# RS-485_Interface.net
KiCad netlist of a schematic drawn in Altium Designer
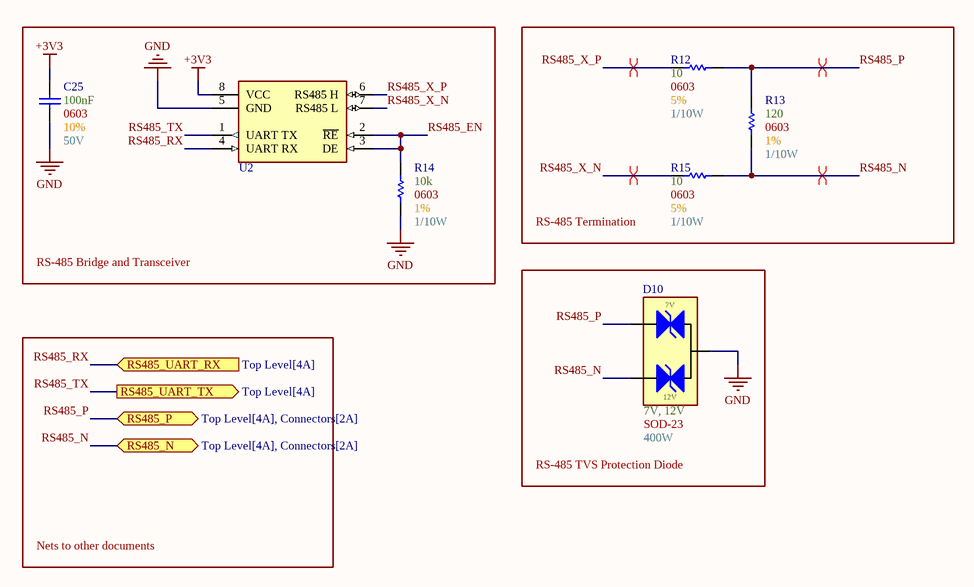
[diagram p0: RS-485 Interface.SchDoc]

(export (version "E")
  (design (tool "Eeschema 10.0.6"))
  (components
    (comp (ref "C25")
      (value "[Cap] 0603 0.1uF 10% 50V")
      (footprint "[Cap] SMD 0603")
      (description "CL10B104KB8NNNC")
      (fields
        (field (name "MAX VOLTAGE") "50V")
        (field (name "SIZE PACKAGE") "0603")
        (field (name "TOLERANCE") "10%")
        (field (name "CAPACITANCE") "100nF")
      )
      (libsource (lib "Capacitors") (part "[Cap] 0603 0.1uF 10% 50V"))
    )
    (comp (ref "D10")
      (value "SOD-23")
      (footprint "SOD-23")
      (description "CDSOT23-SM712")
      (fields (field (name "WATTAGE") "400W") (field (name "OPTIMAL ZENER VOLTAGE") "7V, 12V"))
      (libsource (lib "Diodes") (part "[TVS] 7,12Vnom 11,19Vclamp_max"))
    )
    (comp (ref "R12")
      (value "[10] SMD 0603 5% 1/10W")
      (footprint "[Res] SMD 0603")
      (description "RC0603JR-1310RL")
      (fields
        (field (name "WATTAGE") "1/10W")
        (field (name "TOLERANCE") "5%")
        (field (name "RESISTANCE") "10")
        (field (name "SIZE PACKAGE") "0603")
      )
      (libsource (lib "Resistors") (part "[10] SMD 0603 5% 1/10W"))
    )
    (comp (ref "R13")
      (value "[120] SMD 0603 1% 1/10W")
      (footprint "[Res] SMD 0603")
      (description "RC0603FR-07120RL")
      (fields
        (field (name "WATTAGE") "1/10W")
        (field (name "TOLERANCE") "1%")
        (field (name "RESISTANCE") "120")
        (field (name "SIZE PACKAGE") "0603")
      )
      (libsource (lib "Resistors") (part "[120] SMD 0603 1% 1/10W"))
    )
    (comp (ref "R14")
      (value "[10k] SMD 0603 1% 1/10W")
      (footprint "[Res] SMD 0603")
      (description "RMCF0603FT10K0")
      (fields
        (field (name "WATTAGE") "1/10W")
        (field (name "TOLERANCE") "1%")
        (field (name "RESISTANCE") "10k")
        (field (name "SIZE PACKAGE") "0603")
      )
      (libsource (lib "Resistors") (part "[10k] SMD 0603 1% 1/10W"))
    )
    (comp (ref "R15")
      (value "[10] SMD 0603 5% 1/10W")
      (footprint "[Res] SMD 0603")
      (description "RC0603JR-1310RL")
      (fields
        (field (name "WATTAGE") "1/10W")
        (field (name "TOLERANCE") "5%")
        (field (name "RESISTANCE") "10")
        (field (name "SIZE PACKAGE") "0603")
      )
      (libsource (lib "Resistors") (part "[10] SMD 0603 5% 1/10W"))
    )
    (comp (ref "U2")
      (value "[Bridge] UART-RS485")
      (footprint "8-SOIC")
      (description "THVD1400DR")
      (libsource (lib "ICs") (part "[Bridge] UART-RS485"))
    )
  )
  (nets
    (net (code "1") (name "+3V3") (class "Default")
      (node (ref "C25") (pin "2") (pinfunction "2_2") (pintype "passive"))
      (node (ref "U2") (pin "8") (pinfunction "VCC_8") (pintype "passive"))
    )
    (net (code "2") (name "/RS485_EN") (class "Default")
      (node (ref "R14") (pin "2") (pinfunction "2_2") (pintype "passive"))
      (node (ref "U2") (pin "2") (pinfunction "~{RE}_2") (pintype "input"))
      (node (ref "U2") (pin "3") (pinfunction "DE_3") (pintype "input"))
    )
    (net (code "3") (name "/RS485_N") (class "Default")
      (node (ref "D10") (pin "2") (pintype "passive"))
      (node (ref "R13") (pin "1") (pinfunction "1_1") (pintype "passive"))
      (node (ref "R15") (pin "1") (pinfunction "1_1") (pintype "passive"))
    )
    (net (code "4") (name "/RS485_P") (class "Default")
      (node (ref "D10") (pin "1") (pintype "passive"))
      (node (ref "R12") (pin "1") (pinfunction "1_1") (pintype "passive"))
      (node (ref "R13") (pin "2") (pinfunction "2_2") (pintype "passive"))
    )
    (net (code "5") (name "/RS485_RX") (class "Default")
      (node (ref "U2") (pin "4") (pinfunction "UART_RX_4") (pintype "input"))
    )
    (net (code "6") (name "/RS485_TX") (class "Default")
      (node (ref "U2") (pin "1") (pinfunction "UART_TX_1") (pintype "output"))
    )
    (net (code "7") (name "/RS485_X_N") (class "Default")
      (node (ref "R15") (pin "2") (pinfunction "2_2") (pintype "passive"))
      (node (ref "U2") (pin "7") (pinfunction "RS485_L_7") (pintype "bidirectional"))
    )
    (net (code "8") (name "/RS485_X_P") (class "Default")
      (node (ref "R12") (pin "2") (pinfunction "2_2") (pintype "passive"))
      (node (ref "U2") (pin "6") (pinfunction "RS485_H_6") (pintype "bidirectional"))
    )
    (net (code "9") (name "GND") (class "Default")
      (node (ref "C25") (pin "1") (pinfunction "1_1") (pintype "passive"))
      (node (ref "D10") (pin "3") (pintype "passive"))
      (node (ref "R14") (pin "1") (pinfunction "1_1") (pintype "passive"))
      (node (ref "U2") (pin "5") (pinfunction "GND_5") (pintype "passive"))
    )
  )
)
